# DCM_y_ULTRASONIDO_1_3.net
KiCad netlist of a schematic drawn in Altium Designer
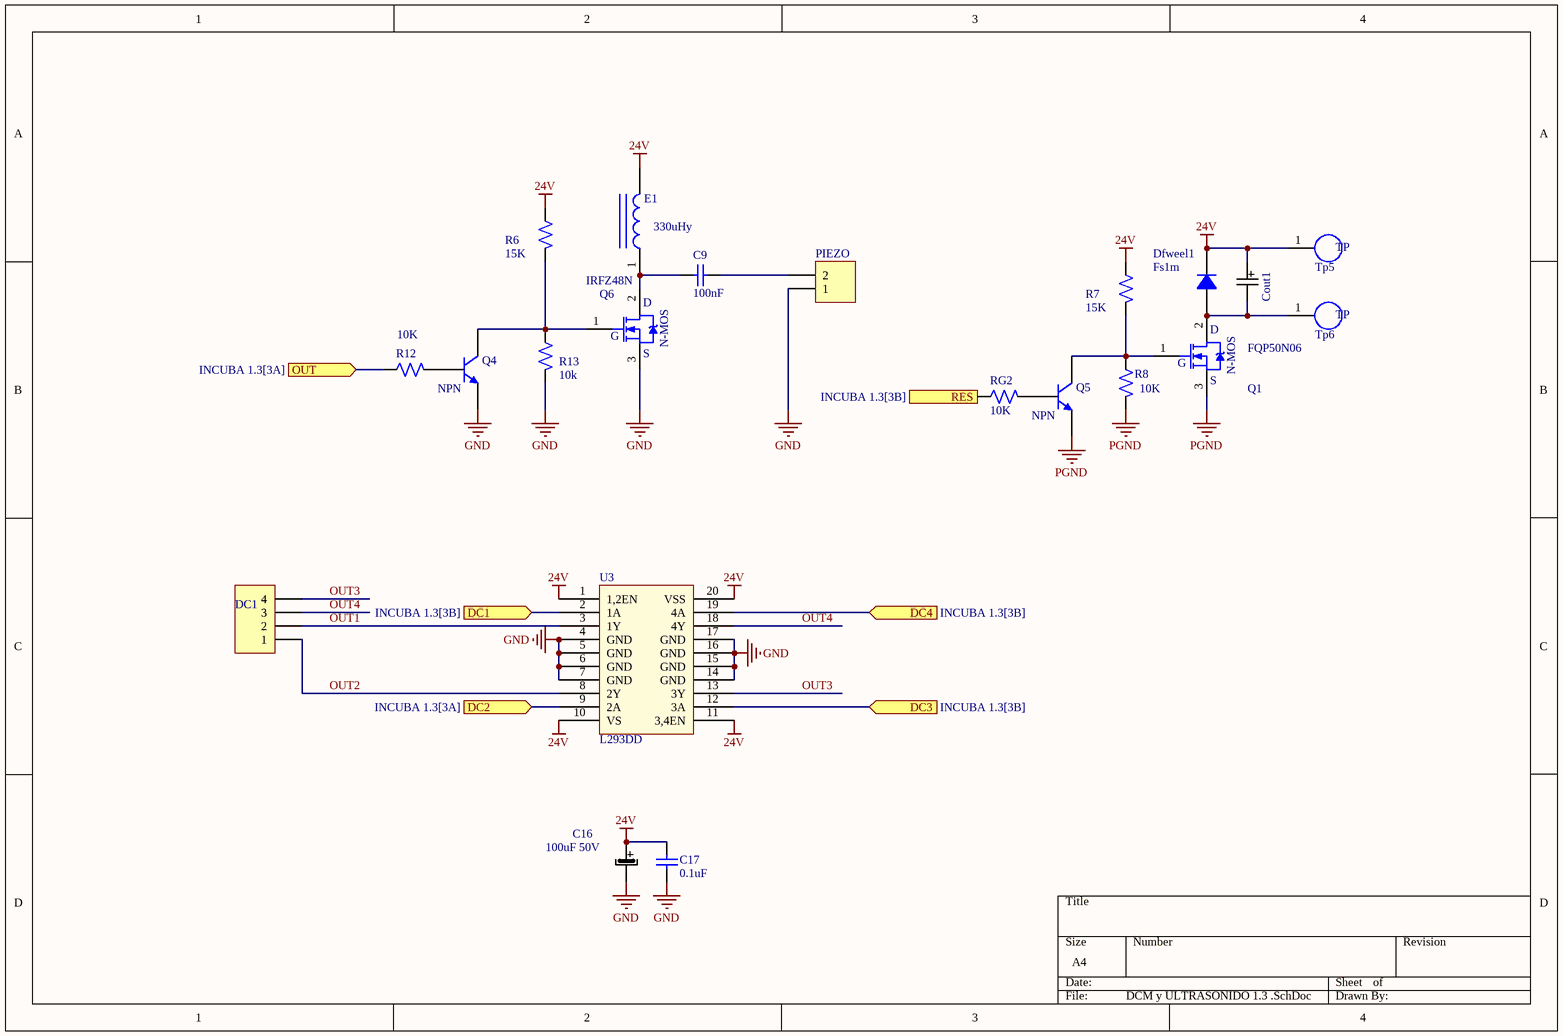
[diagram p0: DCM y ULTRASONIDO 1.3 .SchDoc]

(export (version "E")
  (design (tool "Eeschema 10.0.6"))
  (components
    (comp (ref "C9")
      (value "100nF")
      (footprint "0805")
      (description "Capacitor")
      (fields (field (name "PUBLISHER") "Altium Limited"))
      (libsource (lib "marcelo") (part "Cap SMD"))
    )
    (comp (ref "C16")
      (value "100uF 50V")
      (footprint "cap100")
      (description "Capacitor Polarizado")
      (fields (field (name "Comment") "Capacitor"))
      (libsource (lib "daniel") (part "Capacitor_Polarizado"))
    )
    (comp (ref "C17")
      (value "0.1uF")
      (footprint "0805")
      (description "Capacitor")
      (fields (field (name "PUBLISHER") "Altium Limited"))
      (libsource (lib "marcelo") (part "Cap SMD"))
    )
    (comp (ref "Cout1")
      (value "Cout")
      (footprint "0805")
      (description "Capacitor")
      (libsource (lib "daniel") (part "Capacitor"))
    )
    (comp (ref "DC1")
      (value "Header 4")
      (footprint "HDR1X4")
      (description "Header, 4-Pin")
      (fields (field (name "PUBLISHER") "Altium Limited"))
      (libsource (lib "Miscellaneous Connectors") (part "Header 4"))
    )
    (comp (ref "Dfweel1")
      (value "Fs1m")
      (footprint "DO-214AC")
      (description "DSK14 , US1M. Fs1m")
      (fields (field (name "PUBLISHER") "Altium Limited"))
      (libsource (lib "daniel") (part "Diodo"))
    )
    (comp (ref "E1")
      (value "330uHy")
      (footprint "res200")
      (description "Magnetic-Core Inductor")
      (fields (field (name "Comment") "Inductor Iron") (field (name "PUBLISHER") "Altium Limited"))
      (libsource (lib "daniel") (part "Inductor Iron"))
    )
    (comp (ref "PIEZO")
      (value "Header 2")
      (footprint "HDR1X2")
      (description "Header, 2-Pin")
      (fields (field (name "PUBLISHER") "Altium Limited"))
      (libsource (lib "Miscellaneous Connectors") (part "Header 2"))
    )
    (comp (ref "Q1")
      (value "FQP50N06")
      (footprint "TO-220")
      (description "IRLZ44")
      (fields (field (name "PUBLISHER") "Altium Limited"))
      (libsource (lib "daniel") (part "IRFZ48N"))
    )
    (comp (ref "Q4") (value "NPN") (footprint "SOT23-5_hall") (libsource (lib "daniel") (part "GMBT2222A")))
    (comp (ref "Q5") (value "NPN") (footprint "SOT23-5_hall") (libsource (lib "daniel") (part "GMBT2222A")))
    (comp (ref "Q6")
      (value "IRFZ48N")
      (footprint "TO-220")
      (description "IRLZ44")
      (fields (field (name "PUBLISHER") "Altium Limited"))
      (libsource (lib "daniel") (part "IRFZ48N"))
    )
    (comp (ref "R6")
      (value "15K")
      (footprint "0805")
      (description "Resistencia  de con varios Footprint")
      (fields (field (name "Comment") "Resistencia"))
      (libsource (lib "daniel") (part "Resistencia"))
    )
    (comp (ref "R7")
      (value "15K")
      (footprint "0805")
      (description "Resistencia  de con varios Footprint")
      (fields (field (name "Comment") "Resistencia"))
      (libsource (lib "daniel") (part "Resistencia"))
    )
    (comp (ref "R8")
      (value "10K")
      (footprint "0805")
      (description "Resistencia  de con varios Footprint")
      (fields (field (name "Comment") "Resistencia"))
      (libsource (lib "daniel") (part "Resistencia"))
    )
    (comp (ref "R12")
      (value "10K")
      (footprint "0805")
      (description "Resistencia  de con varios Footprint")
      (fields (field (name "Comment") "Resistencia"))
      (libsource (lib "daniel") (part "Resistencia"))
    )
    (comp (ref "R13")
      (value "10k")
      (footprint "0805")
      (description "Resistencia  de con varios Footprint")
      (fields (field (name "Comment") "Resistencia"))
      (libsource (lib "daniel") (part "Resistencia"))
    )
    (comp (ref "RG2")
      (value "10K")
      (footprint "0805")
      (description "Resistencia  de con varios Footprint")
      (fields (field (name "Comment") "RG"))
      (libsource (lib "daniel") (part "Resistencia"))
    )
    (comp (ref "Tp5")
      (value "Testpoint")
      (footprint "Testpoint")
      (description "Tespoint")
      (libsource (lib "daniel") (part "Testpoint"))
    )
    (comp (ref "Tp6")
      (value "Testpoint")
      (footprint "Testpoint")
      (description "Tespoint")
      (libsource (lib "daniel") (part "Testpoint"))
    )
    (comp (ref "U3")
      (value "L293DD")
      (footprint "SOIC127P1032X265-20N")
      (libsource (lib "daniel") (part "L293DD"))
    )
  )
  (nets
    (net (code "1") (name "/DC1") (class "Default")
      (node (ref "U3") (pin "2") (pinfunction "1A_2") (pintype "passive"))
    )
    (net (code "2") (name "/DC2") (class "Default")
      (node (ref "U3") (pin "9") (pinfunction "2A_9") (pintype "passive"))
    )
    (net (code "3") (name "/DC3") (class "Default")
      (node (ref "U3") (pin "12") (pinfunction "3A_12") (pintype "passive"))
    )
    (net (code "4") (name "/DC4") (class "Default")
      (node (ref "U3") (pin "19") (pinfunction "4A_19") (pintype "passive"))
    )
    (net (code "5") (name "/OUT") (class "Default")
      (node (ref "R12") (pin "2") (pinfunction "2_2") (pintype "passive"))
    )
    (net (code "6") (name "/OUT1") (class "Default")
      (node (ref "DC1") (pin "2") (pinfunction "2_2") (pintype "passive"))
      (node (ref "U3") (pin "3") (pinfunction "1Y_3") (pintype "passive"))
    )
    (net (code "7") (name "/OUT2") (class "Default")
      (node (ref "DC1") (pin "1") (pinfunction "1_1") (pintype "passive"))
      (node (ref "U3") (pin "8") (pinfunction "2Y_8") (pintype "passive"))
    )
    (net (code "8") (name "/OUT3") (class "Default")
      (node (ref "DC1") (pin "4") (pinfunction "4_4") (pintype "passive"))
      (node (ref "U3") (pin "13") (pinfunction "3Y_13") (pintype "passive"))
    )
    (net (code "9") (name "/OUT4") (class "Default")
      (node (ref "DC1") (pin "3") (pinfunction "3_3") (pintype "passive"))
      (node (ref "U3") (pin "18") (pinfunction "4Y_18") (pintype "passive"))
    )
    (net (code "10") (name "/RES") (class "Default")
      (node (ref "RG2") (pin "1") (pinfunction "1_1") (pintype "passive"))
    )
    (net (code "11") (name "24V") (class "Default")
      (node (ref "C16") (pin "2") (pinfunction "2_2") (pintype "passive"))
      (node (ref "C17") (pin "1") (pinfunction "1_1") (pintype "passive"))
      (node (ref "Cout1") (pin "2") (pinfunction "2_2") (pintype "passive"))
      (node (ref "Dfweel1") (pin "1") (pinfunction "K_1") (pintype "passive"))
      (node (ref "E1") (pin "2") (pinfunction "2_2") (pintype "passive"))
      (node (ref "R6") (pin "2") (pinfunction "2_2") (pintype "passive"))
      (node (ref "R7") (pin "2") (pinfunction "2_2") (pintype "passive"))
      (node (ref "Tp5") (pin "1") (pinfunction "TP_1") (pintype "passive"))
      (node (ref "U3") (pin "1") (pinfunction "1,2EN_1") (pintype "passive"))
      (node (ref "U3") (pin "10") (pinfunction "VS_10") (pintype "passive"))
      (node (ref "U3") (pin "11") (pinfunction "3,4EN_11") (pintype "passive"))
      (node (ref "U3") (pin "20") (pinfunction "VSS_20") (pintype "passive"))
    )
    (net (code "12") (name "GND") (class "Default")
      (node (ref "C16") (pin "1") (pinfunction "1_1") (pintype "power_in"))
      (node (ref "C17") (pin "2") (pinfunction "2_2") (pintype "passive"))
      (node (ref "PIEZO") (pin "1") (pinfunction "1_1") (pintype "passive"))
      (node (ref "Q4") (pin "2") (pinfunction "E_2") (pintype "passive"))
      (node (ref "Q6") (pin "3") (pinfunction "S_3") (pintype "passive"))
      (node (ref "R13") (pin "1") (pinfunction "1_1") (pintype "passive"))
      (node (ref "U3") (pin "14") (pinfunction "GND_14") (pintype "passive"))
      (node (ref "U3") (pin "15") (pinfunction "GND_15") (pintype "passive"))
      (node (ref "U3") (pin "16") (pinfunction "GND_16") (pintype "passive"))
      (node (ref "U3") (pin "17") (pinfunction "GND_17") (pintype "passive"))
      (node (ref "U3") (pin "4") (pinfunction "GND_4") (pintype "passive"))
      (node (ref "U3") (pin "5") (pinfunction "GND_5") (pintype "passive"))
      (node (ref "U3") (pin "6") (pinfunction "GND_6") (pintype "passive"))
      (node (ref "U3") (pin "7") (pinfunction "GND_7") (pintype "passive"))
    )
    (net (code "13") (name "Net-(C9-Pad2)") (class "Default")
      (node (ref "C9") (pin "2") (pinfunction "2_2") (pintype "passive"))
      (node (ref "PIEZO") (pin "2") (pinfunction "2_2") (pintype "passive"))
    )
    (net (code "14") (name "Net-(Dfweel1-A)") (class "Default")
      (node (ref "Cout1") (pin "1") (pinfunction "1_1") (pintype "power_in"))
      (node (ref "Dfweel1") (pin "2") (pinfunction "A_2") (pintype "passive"))
      (node (ref "Q1") (pin "2") (pinfunction "D_2") (pintype "passive"))
      (node (ref "Tp6") (pin "1") (pinfunction "TP_1") (pintype "passive"))
    )
    (net (code "15") (name "Net-(Q1-G)") (class "Default")
      (node (ref "Q1") (pin "1") (pinfunction "G_1") (pintype "passive"))
      (node (ref "Q5") (pin "3") (pinfunction "C_3") (pintype "passive"))
      (node (ref "R7") (pin "1") (pinfunction "1_1") (pintype "passive"))
      (node (ref "R8") (pin "2") (pinfunction "2_2") (pintype "passive"))
    )
    (net (code "16") (name "Net-(Q4-B)") (class "Default")
      (node (ref "Q4") (pin "1") (pinfunction "B_1") (pintype "passive"))
      (node (ref "R12") (pin "1") (pinfunction "1_1") (pintype "passive"))
    )
    (net (code "17") (name "Net-(Q4-C)") (class "Default")
      (node (ref "Q4") (pin "3") (pinfunction "C_3") (pintype "passive"))
      (node (ref "Q6") (pin "1") (pinfunction "G_1") (pintype "passive"))
      (node (ref "R13") (pin "2") (pinfunction "2_2") (pintype "passive"))
      (node (ref "R6") (pin "1") (pinfunction "1_1") (pintype "passive"))
    )
    (net (code "18") (name "Net-(Q5-B)") (class "Default")
      (node (ref "Q5") (pin "1") (pinfunction "B_1") (pintype "passive"))
      (node (ref "RG2") (pin "2") (pinfunction "2_2") (pintype "passive"))
    )
    (net (code "19") (name "Net-(Q6-D)") (class "Default")
      (node (ref "C9") (pin "1") (pinfunction "1_1") (pintype "passive"))
      (node (ref "E1") (pin "1") (pinfunction "1_1") (pintype "passive"))
      (node (ref "Q6") (pin "2") (pinfunction "D_2") (pintype "passive"))
    )
    (net (code "20") (name "PGND") (class "Default")
      (node (ref "Q1") (pin "3") (pinfunction "S_3") (pintype "passive"))
      (node (ref "Q5") (pin "2") (pinfunction "E_2") (pintype "passive"))
      (node (ref "R8") (pin "1") (pinfunction "1_1") (pintype "passive"))
    )
  )
)
